# XNOR_gate.net
KiCad netlist of a schematic drawn in EAGLE
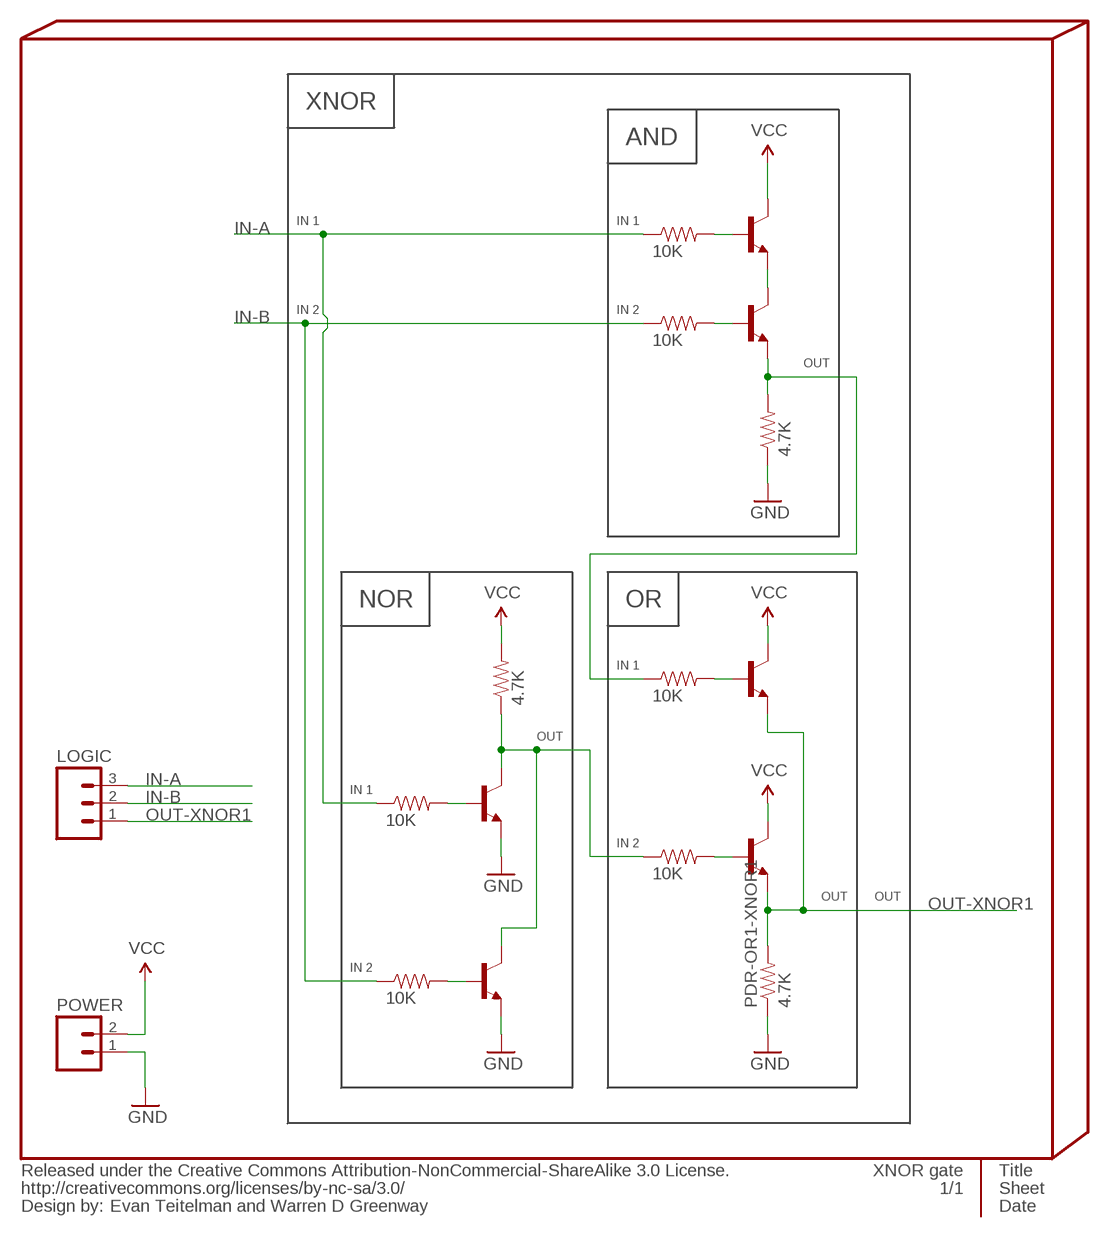
[diagram p0: schematic, sheet 1]

(export (version "E")
  (design (tool "Eeschema 10.0.6"))
  (components
    (comp (ref "INFO4")
      (value "Evan Teitelman and Warren D Greenway")
      (footprint "eagle-import:%CC-NC-SA")
      (libsource (lib "eagle-import") (part "%CC-NC-SA"))
    )
    (comp (ref "LOGIC")
      (value "M03PTH")
      (footprint "eagle-import:1X03")
      (libsource (lib "eagle-import") (part "M03PTH"))
    )
    (comp (ref "PDR-AND1-XNOR1")
      (value "4.7K")
      (footprint "eagle-import:0402-RES")
      (libsource (lib "eagle-import") (part "RESISTOR0402-RES"))
    )
    (comp (ref "PDR-OR1-XNOR1")
      (value "4.7K")
      (footprint "eagle-import:0402-RES")
      (libsource (lib "eagle-import") (part "RESISTOR0402-RES"))
    )
    (comp (ref "POWER")
      (value "M02PTH")
      (footprint "eagle-import:1X02")
      (libsource (lib "eagle-import") (part "M02PTH"))
    )
    (comp (ref "PUR-NOR1-XNOR1")
      (value "4.7K")
      (footprint "eagle-import:0402-RES")
      (libsource (lib "eagle-import") (part "RESISTOR0402-RES"))
    )
    (comp (ref "Q1-AND1-XNOR1")
      (value "TRANSISTOR_NPNSOT23")
      (footprint "eagle-import:SOT23")
      (libsource (lib "eagle-import") (part "TRANSISTOR_NPNSOT23"))
    )
    (comp (ref "Q1-NOR1-XNOR1")
      (value "TRANSISTOR_NPNSOT23")
      (footprint "eagle-import:SOT23")
      (libsource (lib "eagle-import") (part "TRANSISTOR_NPNSOT23"))
    )
    (comp (ref "Q1-OR1-XNOR1")
      (value "TRANSISTOR_NPNSOT23")
      (footprint "eagle-import:SOT23")
      (libsource (lib "eagle-import") (part "TRANSISTOR_NPNSOT23"))
    )
    (comp (ref "Q2-AND1-XNOR1")
      (value "TRANSISTOR_NPNSOT23")
      (footprint "eagle-import:SOT23")
      (libsource (lib "eagle-import") (part "TRANSISTOR_NPNSOT23"))
    )
    (comp (ref "Q2-NOR1-XNOR1")
      (value "TRANSISTOR_NPNSOT23")
      (footprint "eagle-import:SOT23")
      (libsource (lib "eagle-import") (part "TRANSISTOR_NPNSOT23"))
    )
    (comp (ref "Q2-OR1-XNOR1")
      (value "TRANSISTOR_NPNSOT23")
      (footprint "eagle-import:SOT23")
      (libsource (lib "eagle-import") (part "TRANSISTOR_NPNSOT23"))
    )
    (comp (ref "R1-AND1-XNOR1")
      (value "10K")
      (footprint "eagle-import:0402-RES")
      (libsource (lib "eagle-import") (part "RESISTOR0402-RES"))
    )
    (comp (ref "R1-NOR1-XNOR1")
      (value "10K")
      (footprint "eagle-import:0402-RES")
      (libsource (lib "eagle-import") (part "RESISTOR0402-RES"))
    )
    (comp (ref "R1-OR1-XNOR1")
      (value "10K")
      (footprint "eagle-import:0402-RES")
      (libsource (lib "eagle-import") (part "RESISTOR0402-RES"))
    )
    (comp (ref "R2-AND1-XNOR1")
      (value "10K")
      (footprint "eagle-import:0402-RES")
      (libsource (lib "eagle-import") (part "RESISTOR0402-RES"))
    )
    (comp (ref "R2-NOR1-XNOR1")
      (value "10K")
      (footprint "eagle-import:0402-RES")
      (libsource (lib "eagle-import") (part "RESISTOR0402-RES"))
    )
    (comp (ref "R2-OR1-XNOR1")
      (value "10K")
      (footprint "eagle-import:0402-RES")
      (libsource (lib "eagle-import") (part "RESISTOR0402-RES"))
    )
  )
  (nets
    (net (code "1") (name "/IN-A") (class "Default")
      (node (ref "LOGIC") (pin "3") (pinfunction "3_3") (pintype "passive"))
      (node (ref "R1-AND1-XNOR1") (pin "1") (pinfunction "1_1") (pintype "passive"))
      (node (ref "R1-NOR1-XNOR1") (pin "1") (pinfunction "1_1") (pintype "passive"))
    )
    (net (code "2") (name "/IN-B") (class "Default")
      (node (ref "LOGIC") (pin "2") (pinfunction "2_2") (pintype "passive"))
      (node (ref "R2-AND1-XNOR1") (pin "1") (pinfunction "1_1") (pintype "passive"))
      (node (ref "R2-NOR1-XNOR1") (pin "1") (pinfunction "1_1") (pintype "passive"))
    )
    (net (code "3") (name "/OUT-XNOR1") (class "Default")
      (node (ref "LOGIC") (pin "1") (pinfunction "1_1") (pintype "passive"))
      (node (ref "PDR-OR1-XNOR1") (pin "2") (pinfunction "2_2") (pintype "passive"))
      (node (ref "Q1-OR1-XNOR1") (pin "2") (pinfunction "E_2") (pintype "passive"))
      (node (ref "Q2-OR1-XNOR1") (pin "2") (pinfunction "E_2") (pintype "passive"))
    )
    (net (code "4") (name "@GND") (class "Default")
      (node (ref "PDR-AND1-XNOR1") (pin "1") (pinfunction "1_1") (pintype "passive"))
      (node (ref "PDR-OR1-XNOR1") (pin "1") (pinfunction "1_1") (pintype "passive"))
      (node (ref "POWER") (pin "1") (pinfunction "1_1") (pintype "passive"))
      (node (ref "Q1-NOR1-XNOR1") (pin "2") (pinfunction "E_2") (pintype "passive"))
      (node (ref "Q2-NOR1-XNOR1") (pin "2") (pinfunction "E_2") (pintype "passive"))
    )
    (net (code "5") (name "@VCC") (class "Default")
      (node (ref "POWER") (pin "2") (pinfunction "2_2") (pintype "passive"))
      (node (ref "PUR-NOR1-XNOR1") (pin "2") (pinfunction "2_2") (pintype "passive"))
      (node (ref "Q1-AND1-XNOR1") (pin "3") (pinfunction "C_3") (pintype "passive"))
      (node (ref "Q1-OR1-XNOR1") (pin "3") (pinfunction "C_3") (pintype "passive"))
      (node (ref "Q2-OR1-XNOR1") (pin "3") (pinfunction "C_3") (pintype "passive"))
    )
    (net (code "6") (name "Net-(Q1-AND1-XNOR1-B)") (class "Default")
      (node (ref "Q1-AND1-XNOR1") (pin "1") (pinfunction "B_1") (pintype "passive"))
      (node (ref "R1-AND1-XNOR1") (pin "2") (pinfunction "2_2") (pintype "passive"))
    )
    (net (code "7") (name "Net-(Q1-AND1-XNOR1-E)") (class "Default")
      (node (ref "Q1-AND1-XNOR1") (pin "2") (pinfunction "E_2") (pintype "passive"))
      (node (ref "Q2-AND1-XNOR1") (pin "3") (pinfunction "C_3") (pintype "passive"))
    )
    (net (code "8") (name "Net-(Q1-NOR1-XNOR1-B)") (class "Default")
      (node (ref "Q1-NOR1-XNOR1") (pin "1") (pinfunction "B_1") (pintype "passive"))
      (node (ref "R1-NOR1-XNOR1") (pin "2") (pinfunction "2_2") (pintype "passive"))
    )
    (net (code "9") (name "Net-(Q1-NOR1-XNOR1-C)") (class "Default")
      (node (ref "PUR-NOR1-XNOR1") (pin "1") (pinfunction "1_1") (pintype "passive"))
      (node (ref "Q1-NOR1-XNOR1") (pin "3") (pinfunction "C_3") (pintype "passive"))
      (node (ref "Q2-NOR1-XNOR1") (pin "3") (pinfunction "C_3") (pintype "passive"))
      (node (ref "R2-OR1-XNOR1") (pin "1") (pinfunction "1_1") (pintype "passive"))
    )
    (net (code "10") (name "Net-(Q1-OR1-XNOR1-B)") (class "Default")
      (node (ref "Q1-OR1-XNOR1") (pin "1") (pinfunction "B_1") (pintype "passive"))
      (node (ref "R1-OR1-XNOR1") (pin "2") (pinfunction "2_2") (pintype "passive"))
    )
    (net (code "11") (name "Net-(Q2-AND1-XNOR1-B)") (class "Default")
      (node (ref "Q2-AND1-XNOR1") (pin "1") (pinfunction "B_1") (pintype "passive"))
      (node (ref "R2-AND1-XNOR1") (pin "2") (pinfunction "2_2") (pintype "passive"))
    )
    (net (code "12") (name "Net-(Q2-AND1-XNOR1-E)") (class "Default")
      (node (ref "PDR-AND1-XNOR1") (pin "2") (pinfunction "2_2") (pintype "passive"))
      (node (ref "Q2-AND1-XNOR1") (pin "2") (pinfunction "E_2") (pintype "passive"))
      (node (ref "R1-OR1-XNOR1") (pin "1") (pinfunction "1_1") (pintype "passive"))
    )
    (net (code "13") (name "Net-(Q2-NOR1-XNOR1-B)") (class "Default")
      (node (ref "Q2-NOR1-XNOR1") (pin "1") (pinfunction "B_1") (pintype "passive"))
      (node (ref "R2-NOR1-XNOR1") (pin "2") (pinfunction "2_2") (pintype "passive"))
    )
    (net (code "14") (name "Net-(Q2-OR1-XNOR1-B)") (class "Default")
      (node (ref "Q2-OR1-XNOR1") (pin "1") (pinfunction "B_1") (pintype "passive"))
      (node (ref "R2-OR1-XNOR1") (pin "2") (pinfunction "2_2") (pintype "passive"))
    )
  )
)
